# teensyShield1_2.net
KiCad netlist of a schematic drawn in EAGLE
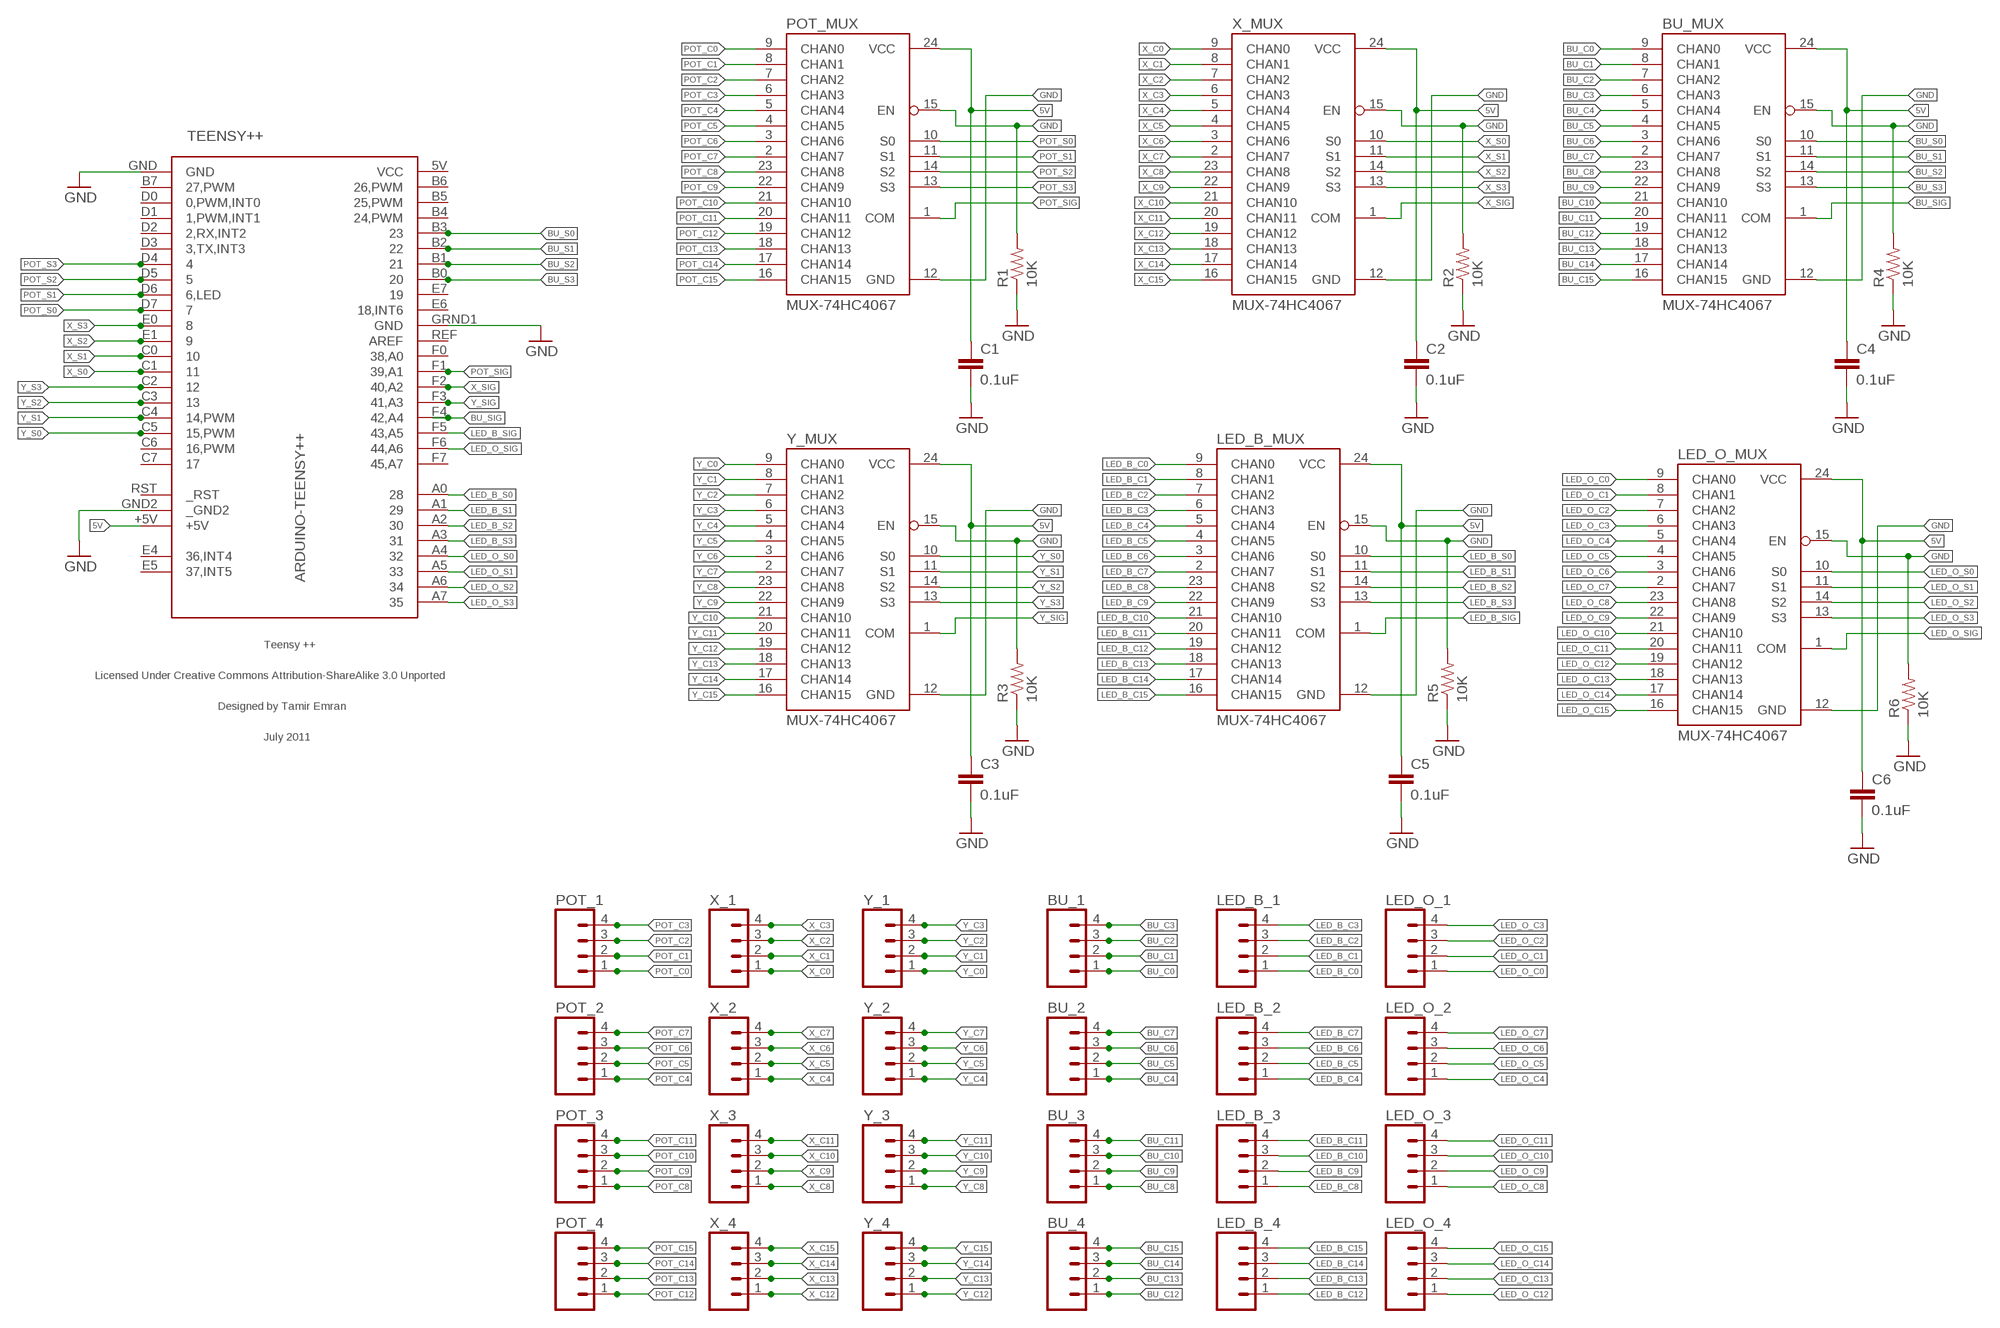
[diagram p0: schematic, sheet 1]

(export (version "E")
  (design (tool "Eeschema 10.0.6"))
  (components
    (comp (ref "BU_1")
      (value "M04NO_SILK_ALL_ROUND")
      (footprint "eagle-import:1X04_NO_SILK_ALL_ROUND")
      (libsource (lib "eagle-import") (part "M04NO_SILK_ALL_ROUND"))
    )
    (comp (ref "BU_2")
      (value "M04NO_SILK_ALL_ROUND")
      (footprint "eagle-import:1X04_NO_SILK_ALL_ROUND")
      (libsource (lib "eagle-import") (part "M04NO_SILK_ALL_ROUND"))
    )
    (comp (ref "BU_3")
      (value "M04NO_SILK_ALL_ROUND")
      (footprint "eagle-import:1X04_NO_SILK_ALL_ROUND")
      (libsource (lib "eagle-import") (part "M04NO_SILK_ALL_ROUND"))
    )
    (comp (ref "BU_4")
      (value "M04NO_SILK_ALL_ROUND")
      (footprint "eagle-import:1X04_NO_SILK_ALL_ROUND")
      (libsource (lib "eagle-import") (part "M04NO_SILK_ALL_ROUND"))
    )
    (comp (ref "BU_MUX")
      (value "MUX-74HC4067")
      (footprint "eagle-import:SSOP24")
      (libsource (lib "eagle-import") (part "MUX-74HC4067SMD"))
    )
    (comp (ref "C1")
      (value "0.1uF")
      (footprint "eagle-import:0603")
      (libsource (lib "eagle-import") (part "CAP0603"))
    )
    (comp (ref "C2")
      (value "0.1uF")
      (footprint "eagle-import:0603")
      (libsource (lib "eagle-import") (part "CAP0603"))
    )
    (comp (ref "C3")
      (value "0.1uF")
      (footprint "eagle-import:0603")
      (libsource (lib "eagle-import") (part "CAP0603"))
    )
    (comp (ref "C4")
      (value "0.1uF")
      (footprint "eagle-import:0603")
      (libsource (lib "eagle-import") (part "CAP0603"))
    )
    (comp (ref "C5")
      (value "0.1uF")
      (footprint "eagle-import:0603")
      (libsource (lib "eagle-import") (part "CAP0603"))
    )
    (comp (ref "C6")
      (value "0.1uF")
      (footprint "eagle-import:0603")
      (libsource (lib "eagle-import") (part "CAP0603"))
    )
    (comp (ref "LED_B_1")
      (value "M04NO_SILK_ALL_ROUND")
      (footprint "eagle-import:1X04_NO_SILK_ALL_ROUND")
      (libsource (lib "eagle-import") (part "M04NO_SILK_ALL_ROUND"))
    )
    (comp (ref "LED_B_2")
      (value "M04NO_SILK_ALL_ROUND")
      (footprint "eagle-import:1X04_NO_SILK_ALL_ROUND")
      (libsource (lib "eagle-import") (part "M04NO_SILK_ALL_ROUND"))
    )
    (comp (ref "LED_B_3")
      (value "M04NO_SILK_ALL_ROUND")
      (footprint "eagle-import:1X04_NO_SILK_ALL_ROUND")
      (libsource (lib "eagle-import") (part "M04NO_SILK_ALL_ROUND"))
    )
    (comp (ref "LED_B_4")
      (value "M04NO_SILK_ALL_ROUND")
      (footprint "eagle-import:1X04_NO_SILK_ALL_ROUND")
      (libsource (lib "eagle-import") (part "M04NO_SILK_ALL_ROUND"))
    )
    (comp (ref "LED_B_MUX")
      (value "MUX-74HC4067")
      (footprint "eagle-import:SSOP24")
      (libsource (lib "eagle-import") (part "MUX-74HC4067SMD"))
    )
    (comp (ref "LED_O_1")
      (value "M04NO_SILK_ALL_ROUND")
      (footprint "eagle-import:1X04_NO_SILK_ALL_ROUND")
      (libsource (lib "eagle-import") (part "M04NO_SILK_ALL_ROUND"))
    )
    (comp (ref "LED_O_2")
      (value "M04NO_SILK_ALL_ROUND")
      (footprint "eagle-import:1X04_NO_SILK_ALL_ROUND")
      (libsource (lib "eagle-import") (part "M04NO_SILK_ALL_ROUND"))
    )
    (comp (ref "LED_O_3")
      (value "M04NO_SILK_ALL_ROUND")
      (footprint "eagle-import:1X04_NO_SILK_ALL_ROUND")
      (libsource (lib "eagle-import") (part "M04NO_SILK_ALL_ROUND"))
    )
    (comp (ref "LED_O_4")
      (value "M04NO_SILK_ALL_ROUND")
      (footprint "eagle-import:1X04_NO_SILK_ALL_ROUND")
      (libsource (lib "eagle-import") (part "M04NO_SILK_ALL_ROUND"))
    )
    (comp (ref "LED_O_MUX")
      (value "MUX-74HC4067")
      (footprint "eagle-import:SSOP24")
      (libsource (lib "eagle-import") (part "MUX-74HC4067SMD"))
    )
    (comp (ref "POT_1")
      (value "M04NO_SILK_ALL_ROUND")
      (footprint "eagle-import:1X04_NO_SILK_ALL_ROUND")
      (libsource (lib "eagle-import") (part "M04NO_SILK_ALL_ROUND"))
    )
    (comp (ref "POT_2")
      (value "M04NO_SILK_ALL_ROUND")
      (footprint "eagle-import:1X04_NO_SILK_ALL_ROUND")
      (libsource (lib "eagle-import") (part "M04NO_SILK_ALL_ROUND"))
    )
    (comp (ref "POT_3")
      (value "M04NO_SILK_ALL_ROUND")
      (footprint "eagle-import:1X04_NO_SILK_ALL_ROUND")
      (libsource (lib "eagle-import") (part "M04NO_SILK_ALL_ROUND"))
    )
    (comp (ref "POT_4")
      (value "M04NO_SILK_ALL_ROUND")
      (footprint "eagle-import:1X04_NO_SILK_ALL_ROUND")
      (libsource (lib "eagle-import") (part "M04NO_SILK_ALL_ROUND"))
    )
    (comp (ref "POT_MUX")
      (value "MUX-74HC4067")
      (footprint "eagle-import:SSOP24")
      (libsource (lib "eagle-import") (part "MUX-74HC4067SMD"))
    )
    (comp (ref "R1")
      (value "10K")
      (footprint "eagle-import:0603")
      (libsource (lib "eagle-import") (part "RESISTOR0603"))
    )
    (comp (ref "R2")
      (value "10K")
      (footprint "eagle-import:0603")
      (libsource (lib "eagle-import") (part "RESISTOR0603"))
    )
    (comp (ref "R3")
      (value "10K")
      (footprint "eagle-import:0603")
      (libsource (lib "eagle-import") (part "RESISTOR0603"))
    )
    (comp (ref "R4")
      (value "10K")
      (footprint "eagle-import:0603")
      (libsource (lib "eagle-import") (part "RESISTOR0603"))
    )
    (comp (ref "R5")
      (value "10K")
      (footprint "eagle-import:0603")
      (libsource (lib "eagle-import") (part "RESISTOR0603"))
    )
    (comp (ref "R6")
      (value "10K")
      (footprint "eagle-import:0603")
      (libsource (lib "eagle-import") (part "RESISTOR0603"))
    )
    (comp (ref "TEENSY++")
      (value "ARDUINO-TEENSY++")
      (footprint "eagle-import:TEENSY++")
      (libsource (lib "eagle-import") (part "ARDUINO-TEENSY++"))
    )
    (comp (ref "X_1")
      (value "M04NO_SILK_ALL_ROUND")
      (footprint "eagle-import:1X04_NO_SILK_ALL_ROUND")
      (libsource (lib "eagle-import") (part "M04NO_SILK_ALL_ROUND"))
    )
    (comp (ref "X_2")
      (value "M04NO_SILK_ALL_ROUND")
      (footprint "eagle-import:1X04_NO_SILK_ALL_ROUND")
      (libsource (lib "eagle-import") (part "M04NO_SILK_ALL_ROUND"))
    )
    (comp (ref "X_3")
      (value "M04NO_SILK_ALL_ROUND")
      (footprint "eagle-import:1X04_NO_SILK_ALL_ROUND")
      (libsource (lib "eagle-import") (part "M04NO_SILK_ALL_ROUND"))
    )
    (comp (ref "X_4")
      (value "M04NO_SILK_ALL_ROUND")
      (footprint "eagle-import:1X04_NO_SILK_ALL_ROUND")
      (libsource (lib "eagle-import") (part "M04NO_SILK_ALL_ROUND"))
    )
    (comp (ref "X_MUX")
      (value "MUX-74HC4067")
      (footprint "eagle-import:SSOP24")
      (libsource (lib "eagle-import") (part "MUX-74HC4067SMD"))
    )
    (comp (ref "Y_1")
      (value "M04NO_SILK_ALL_ROUND")
      (footprint "eagle-import:1X04_NO_SILK_ALL_ROUND")
      (libsource (lib "eagle-import") (part "M04NO_SILK_ALL_ROUND"))
    )
    (comp (ref "Y_2")
      (value "M04NO_SILK_ALL_ROUND")
      (footprint "eagle-import:1X04_NO_SILK_ALL_ROUND")
      (libsource (lib "eagle-import") (part "M04NO_SILK_ALL_ROUND"))
    )
    (comp (ref "Y_3")
      (value "M04NO_SILK_ALL_ROUND")
      (footprint "eagle-import:1X04_NO_SILK_ALL_ROUND")
      (libsource (lib "eagle-import") (part "M04NO_SILK_ALL_ROUND"))
    )
    (comp (ref "Y_4")
      (value "M04NO_SILK_ALL_ROUND")
      (footprint "eagle-import:1X04_NO_SILK_ALL_ROUND")
      (libsource (lib "eagle-import") (part "M04NO_SILK_ALL_ROUND"))
    )
    (comp (ref "Y_MUX")
      (value "MUX-74HC4067")
      (footprint "eagle-import:SSOP24")
      (libsource (lib "eagle-import") (part "MUX-74HC4067SMD"))
    )
  )
  (nets
    (net (code "1") (name "/VCC") (class "Default")
      (node (ref "TEENSY++") (pin "5V") (pinfunction "VCC_5V") (pintype "power_in"))
    )
    (net (code "2") (name "5V") (class "Default")
      (node (ref "BU_MUX") (pin "24") (pinfunction "VCC_24") (pintype "bidirectional"))
      (node (ref "C1") (pin "1") (pinfunction "1_1") (pintype "passive"))
      (node (ref "C2") (pin "1") (pinfunction "1_1") (pintype "passive"))
      (node (ref "C3") (pin "1") (pinfunction "1_1") (pintype "passive"))
      (node (ref "C4") (pin "1") (pinfunction "1_1") (pintype "passive"))
      (node (ref "C5") (pin "1") (pinfunction "1_1") (pintype "passive"))
      (node (ref "C6") (pin "1") (pinfunction "1_1") (pintype "passive"))
      (node (ref "LED_B_MUX") (pin "24") (pinfunction "VCC_24") (pintype "bidirectional"))
      (node (ref "LED_O_MUX") (pin "24") (pinfunction "VCC_24") (pintype "bidirectional"))
      (node (ref "POT_MUX") (pin "24") (pinfunction "VCC_24") (pintype "bidirectional"))
      (node (ref "X_MUX") (pin "24") (pinfunction "VCC_24") (pintype "bidirectional"))
      (node (ref "Y_MUX") (pin "24") (pinfunction "VCC_24") (pintype "bidirectional"))
    )
    (net (code "3") (name "BU_C0") (class "Default")
      (node (ref "BU_1") (pin "1") (pinfunction "1_1") (pintype "passive"))
      (node (ref "BU_MUX") (pin "9") (pinfunction "CHAN0_9") (pintype "bidirectional"))
    )
    (net (code "4") (name "BU_C1") (class "Default")
      (node (ref "BU_1") (pin "2") (pinfunction "2_2") (pintype "passive"))
      (node (ref "BU_MUX") (pin "8") (pinfunction "CHAN1_8") (pintype "bidirectional"))
    )
    (net (code "5") (name "BU_C2") (class "Default")
      (node (ref "BU_1") (pin "3") (pinfunction "3_3") (pintype "passive"))
      (node (ref "BU_MUX") (pin "7") (pinfunction "CHAN2_7") (pintype "bidirectional"))
    )
    (net (code "6") (name "BU_C3") (class "Default")
      (node (ref "BU_1") (pin "4") (pinfunction "4_4") (pintype "passive"))
      (node (ref "BU_MUX") (pin "6") (pinfunction "CHAN3_6") (pintype "bidirectional"))
    )
    (net (code "7") (name "BU_C4") (class "Default")
      (node (ref "BU_2") (pin "1") (pinfunction "1_1") (pintype "passive"))
      (node (ref "BU_MUX") (pin "5") (pinfunction "CHAN4_5") (pintype "bidirectional"))
    )
    (net (code "8") (name "BU_C5") (class "Default")
      (node (ref "BU_2") (pin "2") (pinfunction "2_2") (pintype "passive"))
      (node (ref "BU_MUX") (pin "4") (pinfunction "CHAN5_4") (pintype "bidirectional"))
    )
    (net (code "9") (name "BU_C6") (class "Default")
      (node (ref "BU_2") (pin "3") (pinfunction "3_3") (pintype "passive"))
      (node (ref "BU_MUX") (pin "3") (pinfunction "CHAN6_3") (pintype "bidirectional"))
    )
    (net (code "10") (name "BU_C7") (class "Default")
      (node (ref "BU_2") (pin "4") (pinfunction "4_4") (pintype "passive"))
      (node (ref "BU_MUX") (pin "2") (pinfunction "CHAN7_2") (pintype "bidirectional"))
    )
    (net (code "11") (name "BU_C8") (class "Default")
      (node (ref "BU_3") (pin "1") (pinfunction "1_1") (pintype "passive"))
      (node (ref "BU_MUX") (pin "23") (pinfunction "CHAN8_23") (pintype "bidirectional"))
    )
    (net (code "12") (name "BU_C9") (class "Default")
      (node (ref "BU_3") (pin "2") (pinfunction "2_2") (pintype "passive"))
      (node (ref "BU_MUX") (pin "22") (pinfunction "CHAN9_22") (pintype "bidirectional"))
    )
    (net (code "13") (name "BU_C10") (class "Default")
      (node (ref "BU_3") (pin "3") (pinfunction "3_3") (pintype "passive"))
      (node (ref "BU_MUX") (pin "21") (pinfunction "CHAN10_21") (pintype "bidirectional"))
    )
    (net (code "14") (name "BU_C11") (class "Default")
      (node (ref "BU_3") (pin "4") (pinfunction "4_4") (pintype "passive"))
      (node (ref "BU_MUX") (pin "20") (pinfunction "CHAN11_20") (pintype "bidirectional"))
    )
    (net (code "15") (name "BU_C12") (class "Default")
      (node (ref "BU_4") (pin "1") (pinfunction "1_1") (pintype "passive"))
      (node (ref "BU_MUX") (pin "19") (pinfunction "CHAN12_19") (pintype "bidirectional"))
    )
    (net (code "16") (name "BU_C13") (class "Default")
      (node (ref "BU_4") (pin "2") (pinfunction "2_2") (pintype "passive"))
      (node (ref "BU_MUX") (pin "18") (pinfunction "CHAN13_18") (pintype "bidirectional"))
    )
    (net (code "17") (name "BU_C14") (class "Default")
      (node (ref "BU_4") (pin "3") (pinfunction "3_3") (pintype "passive"))
      (node (ref "BU_MUX") (pin "17") (pinfunction "CHAN14_17") (pintype "bidirectional"))
    )
    (net (code "18") (name "BU_C15") (class "Default")
      (node (ref "BU_4") (pin "4") (pinfunction "4_4") (pintype "passive"))
      (node (ref "BU_MUX") (pin "16") (pinfunction "CHAN15_16") (pintype "bidirectional"))
    )
    (net (code "19") (name "BU_S0") (class "Default")
      (node (ref "BU_MUX") (pin "10") (pinfunction "S0_10") (pintype "input"))
      (node (ref "TEENSY++") (pin "B3") (pinfunction "23_B3") (pintype "bidirectional"))
    )
    (net (code "20") (name "BU_S1") (class "Default")
      (node (ref "BU_MUX") (pin "11") (pinfunction "S1_11") (pintype "input"))
      (node (ref "TEENSY++") (pin "B2") (pinfunction "22_B2") (pintype "bidirectional"))
    )
    (net (code "21") (name "BU_S2") (class "Default")
      (node (ref "BU_MUX") (pin "14") (pinfunction "S2_14") (pintype "input"))
      (node (ref "TEENSY++") (pin "B1") (pinfunction "21_B1") (pintype "bidirectional"))
    )
    (net (code "22") (name "BU_S3") (class "Default")
      (node (ref "BU_MUX") (pin "13") (pinfunction "S3_13") (pintype "input"))
      (node (ref "TEENSY++") (pin "B0") (pinfunction "20_B0") (pintype "bidirectional"))
    )
    (net (code "23") (name "BU_SIG") (class "Default")
      (node (ref "BU_MUX") (pin "1") (pinfunction "COM_1") (pintype "bidirectional"))
      (node (ref "TEENSY++") (pin "F4") (pinfunction "42,A4_F4") (pintype "bidirectional"))
    )
    (net (code "24") (name "GND") (class "Default")
      (node (ref "BU_MUX") (pin "12") (pinfunction "GND_12") (pintype "bidirectional"))
      (node (ref "BU_MUX") (pin "15") (pinfunction "EN_15") (pintype "input"))
      (node (ref "C1") (pin "2") (pinfunction "2_2") (pintype "passive"))
      (node (ref "C2") (pin "2") (pinfunction "2_2") (pintype "passive"))
      (node (ref "C3") (pin "2") (pinfunction "2_2") (pintype "passive"))
      (node (ref "C4") (pin "2") (pinfunction "2_2") (pintype "passive"))
      (node (ref "C5") (pin "2") (pinfunction "2_2") (pintype "passive"))
      (node (ref "C6") (pin "2") (pinfunction "2_2") (pintype "passive"))
      (node (ref "LED_B_MUX") (pin "12") (pinfunction "GND_12") (pintype "bidirectional"))
      (node (ref "LED_B_MUX") (pin "15") (pinfunction "EN_15") (pintype "input"))
      (node (ref "LED_O_MUX") (pin "12") (pinfunction "GND_12") (pintype "bidirectional"))
      (node (ref "LED_O_MUX") (pin "15") (pinfunction "EN_15") (pintype "input"))
      (node (ref "POT_MUX") (pin "12") (pinfunction "GND_12") (pintype "bidirectional"))
      (node (ref "POT_MUX") (pin "15") (pinfunction "EN_15") (pintype "input"))
      (node (ref "R1") (pin "1") (pinfunction "1_1") (pintype "passive"))
      (node (ref "R1") (pin "2") (pinfunction "2_2") (pintype "passive"))
      (node (ref "R2") (pin "1") (pinfunction "1_1") (pintype "passive"))
      (node (ref "R2") (pin "2") (pinfunction "2_2") (pintype "passive"))
      (node (ref "R3") (pin "1") (pinfunction "1_1") (pintype "passive"))
      (node (ref "R3") (pin "2") (pinfunction "2_2") (pintype "passive"))
      (node (ref "R4") (pin "1") (pinfunction "1_1") (pintype "passive"))
      (node (ref "R4") (pin "2") (pinfunction "2_2") (pintype "passive"))
      (node (ref "R5") (pin "1") (pinfunction "1_1") (pintype "passive"))
      (node (ref "R5") (pin "2") (pinfunction "2_2") (pintype "passive"))
      (node (ref "R6") (pin "1") (pinfunction "1_1") (pintype "passive"))
      (node (ref "R6") (pin "2") (pinfunction "2_2") (pintype "passive"))
      (node (ref "TEENSY++") (pin "GND") (pinfunction "GND_GND") (pintype "power_in"))
      (node (ref "TEENSY++") (pin "GND2") (pinfunction "_GND2_GND2") (pintype "power_in"))
      (node (ref "TEENSY++") (pin "GRND1") (pinfunction "GND_GRND1") (pintype "power_in"))
      (node (ref "X_MUX") (pin "12") (pinfunction "GND_12") (pintype "bidirectional"))
      (node (ref "X_MUX") (pin "15") (pinfunction "EN_15") (pintype "input"))
      (node (ref "Y_MUX") (pin "12") (pinfunction "GND_12") (pintype "bidirectional"))
      (node (ref "Y_MUX") (pin "15") (pinfunction "EN_15") (pintype "input"))
    )
    (net (code "25") (name "LED_B_C0") (class "Default")
      (node (ref "LED_B_1") (pin "1") (pinfunction "1_1") (pintype "passive"))
      (node (ref "LED_B_MUX") (pin "9") (pinfunction "CHAN0_9") (pintype "bidirectional"))
    )
    (net (code "26") (name "LED_B_C1") (class "Default")
      (node (ref "LED_B_1") (pin "2") (pinfunction "2_2") (pintype "passive"))
      (node (ref "LED_B_MUX") (pin "8") (pinfunction "CHAN1_8") (pintype "bidirectional"))
    )
    (net (code "27") (name "LED_B_C2") (class "Default")
      (node (ref "LED_B_1") (pin "3") (pinfunction "3_3") (pintype "passive"))
      (node (ref "LED_B_MUX") (pin "7") (pinfunction "CHAN2_7") (pintype "bidirectional"))
    )
    (net (code "28") (name "LED_B_C3") (class "Default")
      (node (ref "LED_B_1") (pin "4") (pinfunction "4_4") (pintype "passive"))
      (node (ref "LED_B_MUX") (pin "6") (pinfunction "CHAN3_6") (pintype "bidirectional"))
    )
    (net (code "29") (name "LED_B_C4") (class "Default")
      (node (ref "LED_B_2") (pin "1") (pinfunction "1_1") (pintype "passive"))
      (node (ref "LED_B_MUX") (pin "5") (pinfunction "CHAN4_5") (pintype "bidirectional"))
    )
    (net (code "30") (name "LED_B_C5") (class "Default")
      (node (ref "LED_B_2") (pin "2") (pinfunction "2_2") (pintype "passive"))
      (node (ref "LED_B_MUX") (pin "4") (pinfunction "CHAN5_4") (pintype "bidirectional"))
    )
    (net (code "31") (name "LED_B_C6") (class "Default")
      (node (ref "LED_B_2") (pin "3") (pinfunction "3_3") (pintype "passive"))
      (node (ref "LED_B_MUX") (pin "3") (pinfunction "CHAN6_3") (pintype "bidirectional"))
    )
    (net (code "32") (name "LED_B_C7") (class "Default")
      (node (ref "LED_B_2") (pin "4") (pinfunction "4_4") (pintype "passive"))
      (node (ref "LED_B_MUX") (pin "2") (pinfunction "CHAN7_2") (pintype "bidirectional"))
    )
    (net (code "33") (name "LED_B_C8") (class "Default")
      (node (ref "LED_B_3") (pin "1") (pinfunction "1_1") (pintype "passive"))
      (node (ref "LED_B_MUX") (pin "23") (pinfunction "CHAN8_23") (pintype "bidirectional"))
    )
    (net (code "34") (name "LED_B_C9") (class "Default")
      (node (ref "LED_B_3") (pin "2") (pinfunction "2_2") (pintype "passive"))
      (node (ref "LED_B_MUX") (pin "22") (pinfunction "CHAN9_22") (pintype "bidirectional"))
    )
    (net (code "35") (name "LED_B_C10") (class "Default")
      (node (ref "LED_B_3") (pin "3") (pinfunction "3_3") (pintype "passive"))
      (node (ref "LED_B_MUX") (pin "21") (pinfunction "CHAN10_21") (pintype "bidirectional"))
    )
    (net (code "36") (name "LED_B_C11") (class "Default")
      (node (ref "LED_B_3") (pin "4") (pinfunction "4_4") (pintype "passive"))
      (node (ref "LED_B_MUX") (pin "20") (pinfunction "CHAN11_20") (pintype "bidirectional"))
    )
    (net (code "37") (name "LED_B_C12") (class "Default")
      (node (ref "LED_B_4") (pin "1") (pinfunction "1_1") (pintype "passive"))
      (node (ref "LED_B_MUX") (pin "19") (pinfunction "CHAN12_19") (pintype "bidirectional"))
    )
    (net (code "38") (name "LED_B_C13") (class "Default")
      (node (ref "LED_B_4") (pin "2") (pinfunction "2_2") (pintype "passive"))
      (node (ref "LED_B_MUX") (pin "18") (pinfunction "CHAN13_18") (pintype "bidirectional"))
    )
    (net (code "39") (name "LED_B_C14") (class "Default")
      (node (ref "LED_B_4") (pin "3") (pinfunction "3_3") (pintype "passive"))
      (node (ref "LED_B_MUX") (pin "17") (pinfunction "CHAN14_17") (pintype "bidirectional"))
    )
    (net (code "40") (name "LED_B_C15") (class "Default")
      (node (ref "LED_B_4") (pin "4") (pinfunction "4_4") (pintype "passive"))
      (node (ref "LED_B_MUX") (pin "16") (pinfunction "CHAN15_16") (pintype "bidirectional"))
    )
    (net (code "41") (name "LED_B_S0") (class "Default")
      (node (ref "LED_B_MUX") (pin "10") (pinfunction "S0_10") (pintype "input"))
      (node (ref "TEENSY++") (pin "A0") (pinfunction "28_A0") (pintype "bidirectional"))
    )
    (net (code "42") (name "LED_B_S1") (class "Default")
      (node (ref "LED_B_MUX") (pin "11") (pinfunction "S1_11") (pintype "input"))
      (node (ref "TEENSY++") (pin "A1") (pinfunction "29_A1") (pintype "bidirectional"))
    )
    (net (code "43") (name "LED_B_S2") (class "Default")
      (node (ref "LED_B_MUX") (pin "14") (pinfunction "S2_14") (pintype "input"))
      (node (ref "TEENSY++") (pin "A2") (pinfunction "30_A2") (pintype "bidirectional"))
    )
    (net (code "44") (name "LED_B_S3") (class "Default")
      (node (ref "LED_B_MUX") (pin "13") (pinfunction "S3_13") (pintype "input"))
      (node (ref "TEENSY++") (pin "A3") (pinfunction "31_A3") (pintype "bidirectional"))
    )
    (net (code "45") (name "LED_B_SIG") (class "Default")
      (node (ref "LED_B_MUX") (pin "1") (pinfunction "COM_1") (pintype "bidirectional"))
    )
    (net (code "46") (name "LED_O_C0") (class "Default")
      (node (ref "LED_O_1") (pin "1") (pinfunction "1_1") (pintype "passive"))
      (node (ref "LED_O_MUX") (pin "9") (pinfunction "CHAN0_9") (pintype "bidirectional"))
    )
    (net (code "47") (name "LED_O_C1") (class "Default")
      (node (ref "LED_O_1") (pin "2") (pinfunction "2_2") (pintype "passive"))
      (node (ref "LED_O_MUX") (pin "8") (pinfunction "CHAN1_8") (pintype "bidirectional"))
    )
    (net (code "48") (name "LED_O_C2") (class "Default")
      (node (ref "LED_O_1") (pin "3") (pinfunction "3_3") (pintype "passive"))
      (node (ref "LED_O_MUX") (pin "7") (pinfunction "CHAN2_7") (pintype "bidirectional"))
    )
    (net (code "49") (name "LED_O_C3") (class "Default")
      (node (ref "LED_O_1") (pin "4") (pinfunction "4_4") (pintype "passive"))
      (node (ref "LED_O_MUX") (pin "6") (pinfunction "CHAN3_6") (pintype "bidirectional"))
    )
    (net (code "50") (name "LED_O_C4") (class "Default")
      (node (ref "LED_O_2") (pin "1") (pinfunction "1_1") (pintype "passive"))
      (node (ref "LED_O_MUX") (pin "5") (pinfunction "CHAN4_5") (pintype "bidirectional"))
    )
    (net (code "51") (name "LED_O_C5") (class "Default")
      (node (ref "LED_O_2") (pin "2") (pinfunction "2_2") (pintype "passive"))
      (node (ref "LED_O_MUX") (pin "4") (pinfunction "CHAN5_4") (pintype "bidirectional"))
    )
    (net (code "52") (name "LED_O_C6") (class "Default")
      (node (ref "LED_O_2") (pin "3") (pinfunction "3_3") (pintype "passive"))
      (node (ref "LED_O_MUX") (pin "3") (pinfunction "CHAN6_3") (pintype "bidirectional"))
    )
    (net (code "53") (name "LED_O_C7") (class "Default")
      (node (ref "LED_O_2") (pin "4") (pinfunction "4_4") (pintype "passive"))
      (node (ref "LED_O_MUX") (pin "2") (pinfunction "CHAN7_2") (pintype "bidirectional"))
    )
    (net (code "54") (name "LED_O_C8") (class "Default")
      (node (ref "LED_O_3") (pin "1") (pinfunction "1_1") (pintype "passive"))
      (node (ref "LED_O_MUX") (pin "23") (pinfunction "CHAN8_23") (pintype "bidirectional"))
    )
    (net (code "55") (name "LED_O_C9") (class "Default")
      (node (ref "LED_O_3") (pin "2") (pinfunction "2_2") (pintype "passive"))
      (node (ref "LED_O_MUX") (pin "22") (pinfunction "CHAN9_22") (pintype "bidirectional"))
    )
    (net (code "56") (name "LED_O_C10") (class "Default")
      (node (ref "LED_O_3") (pin "3") (pinfunction "3_3") (pintype "passive"))
      (node (ref "LED_O_MUX") (pin "21") (pinfunction "CHAN10_21") (pintype "bidirectional"))
    )
    (net (code "57") (name "LED_O_C11") (class "Default")
      (node (ref "LED_O_3") (pin "4") (pinfunction "4_4") (pintype "passive"))
      (node (ref "LED_O_MUX") (pin "20") (pinfunction "CHAN11_20") (pintype "bidirectional"))
    )
    (net (code "58") (name "LED_O_C12") (class "Default")
      (node (ref "LED_O_4") (pin "1") (pinfunction "1_1") (pintype "passive"))
      (node (ref "LED_O_MUX") (pin "19") (pinfunction "CHAN12_19") (pintype "bidirectional"))
    )
    (net (code "59") (name "LED_O_C13") (class "Default")
      (node (ref "LED_O_4") (pin "2") (pinfunction "2_2") (pintype "passive"))
      (node (ref "LED_O_MUX") (pin "18") (pinfunction "CHAN13_18") (pintype "bidirectional"))
    )
    (net (code "60") (name "LED_O_C14") (class "Default")
      (node (ref "LED_O_4") (pin "3") (pinfunction "3_3") (pintype "passive"))
      (node (ref "LED_O_MUX") (pin "17") (pinfunction "CHAN14_17") (pintype "bidirectional"))
    )
    (net (code "61") (name "LED_O_C15") (class "Default")
      (node (ref "LED_O_4") (pin "4") (pinfunction "4_4") (pintype "passive"))
      (node (ref "LED_O_MUX") (pin "16") (pinfunction "CHAN15_16") (pintype "bidirectional"))
    )
    (net (code "62") (name "LED_O_S0") (class "Default")
      (node (ref "LED_O_MUX") (pin "10") (pinfunction "S0_10") (pintype "input"))
      (node (ref "TEENSY++") (pin "A4") (pinfunction "32_A4") (pintype "bidirectional"))
    )
    (net (code "63") (name "LED_O_S1") (class "Default")
      (node (ref "LED_O_MUX") (pin "11") (pinfunction "S1_11") (pintype "input"))
      (node (ref "TEENSY++") (pin "A5") (pinfunction "33_A5") (pintype "bidirectional"))
    )
    (net (code "64") (name "LED_O_S2") (class "Default")
      (node (ref "LED_O_MUX") (pin "14") (pinfunction "S2_14") (pintype "input"))
      (node (ref "TEENSY++") (pin "A6") (pinfunction "34_A6") (pintype "bidirectional"))
    )
    (net (code "65") (name "LED_O_S3") (class "Default")
      (node (ref "LED_O_MUX") (pin "13") (pinfunction "S3_13") (pintype "input"))
      (node (ref "TEENSY++") (pin "A7") (pinfunction "35_A7") (pintype "bidirectional"))
    )
    (net (code "66") (name "LED_O_SIG") (class "Default")
      (node (ref "LED_O_MUX") (pin "1") (pinfunction "COM_1") (pintype "bidirectional"))
    )
    (net (code "67") (name "POT_C0") (class "Default")
      (node (ref "POT_1") (pin "1") (pinfunction "1_1") (pintype "passive"))
      (node (ref "POT_MUX") (pin "9") (pinfunction "CHAN0_9") (pintype "bidirectional"))
    )
    (net (code "68") (name "POT_C1") (class "Default")
      (node (ref "POT_1") (pin "2") (pinfunction "2_2") (pintype "passive"))
      (node (ref "POT_MUX") (pin "8") (pinfunction "CHAN1_8") (pintype "bidirectional"))
    )
    (net (code "69") (name "POT_C2") (class "Default")
      (node (ref "POT_1") (pin "3") (pinfunction "3_3") (pintype "passive"))
      (node (ref "POT_MUX") (pin "7") (pinfunction "CHAN2_7") (pintype "bidirectional"))
    )
    (net (code "70") (name "POT_C3") (class "Default")
      (node (ref "POT_1") (pin "4") (pinfunction "4_4") (pintype "passive"))
      (node (ref "POT_MUX") (pin "6") (pinfunction "CHAN3_6") (pintype "bidirectional"))
    )
    (net (code "71") (name "POT_C4") (class "Default")
      (node (ref "POT_2") (pin "1") (pinfunction "1_1") (pintype "passive"))
      (node (ref "POT_MUX") (pin "5") (pinfunction "CHAN4_5") (pintype "bidirectional"))
    )
    (net (code "72") (name "POT_C5") (class "Default")
      (node (ref "POT_2") (pin "2") (pinfunction "2_2") (pintype "passive"))
      (node (ref "POT_MUX") (pin "4") (pinfunction "CHAN5_4") (pintype "bidirectional"))
    )
    (net (code "73") (name "POT_C6") (class "Default")
      (node (ref "POT_2") (pin "3") (pinfunction "3_3") (pintype "passive"))
      (node (ref "POT_MUX") (pin "3") (pinfunction "CHAN6_3") (pintype "bidirectional"))
    )
    (net (code "74") (name "POT_C7") (class "Default")
      (node (ref "POT_2") (pin "4") (pinfunction "4_4") (pintype "passive"))
      (node (ref "POT_MUX") (pin "2") (pinfunction "CHAN7_2") (pintype "bidirectional"))
    )
    (net (code "75") (name "POT_C8") (class "Default")
      (node (ref "POT_3") (pin "1") (pinfunction "1_1") (pintype "passive"))
      (node (ref "POT_MUX") (pin "23") (pinfunction "CHAN8_23") (pintype "bidirectional"))
    )
    (net (code "76") (name "POT_C9") (class "Default")
      (node (ref "POT_3") (pin "2") (pinfunction "2_2") (pintype "passive"))
      (node (ref "POT_MUX") (pin "22") (pinfunction "CHAN9_22") (pintype "bidirectional"))
    )
    (net (code "77") (name "POT_C10") (class "Default")
      (node (ref "POT_3") (pin "3") (pinfunction "3_3") (pintype "passive"))
      (node (ref "POT_MUX") (pin "21") (pinfunction "CHAN10_21") (pintype "bidirectional"))
    )
    (net (code "78") (name "POT_C11") (class "Default")
      (node (ref "POT_3") (pin "4") (pinfunction "4_4") (pintype "passive"))
      (node (ref "POT_MUX") (pin "20") (pinfunction "CHAN11_20") (pintype "bidirectional"))
    )
    (net (code "79") (name "POT_C12") (class "Default")
      (node (ref "POT_4") (pin "1") (pinfunction "1_1") (pintype "passive"))
      (node (ref "POT_MUX") (pin "19") (pinfunction "CHAN12_19") (pintype "bidirectional"))
    )
    (net (code "80") (name "POT_C13") (class "Default")
      (node (ref "POT_4") (pin "2") (pinfunction "2_2") (pintype "passive"))
      (node (ref "POT_MUX") (pin "18") (pinfunction "CHAN13_18") (pintype "bidirectional"))
    )
    (net (code "81") (name "POT_C14") (class "Default")
      (node (ref "POT_4") (pin "3") (pinfunction "3_3") (pintype "passive"))
      (node (ref "POT_MUX") (pin "17") (pinfunction "CHAN14_17") (pintype "bidirectional"))
    )
    (net (code "82") (name "POT_C15") (class "Default")
      (node (ref "POT_4") (pin "4") (pinfunction "4_4") (pintype "passive"))
      (node (ref "POT_MUX") (pin "16") (pinfunction "CHAN15_16") (pintype "bidirectional"))
    )
    (net (code "83") (name "POT_S0") (class "Default")
      (node (ref "POT_MUX") (pin "10") (pinfunction "S0_10") (pintype "input"))
      (node (ref "TEENSY++") (pin "D7") (pinfunction "7_D7") (pintype "bidirectional"))
    )
    (net (code "84") (name "POT_S1") (class "Default")
      (node (ref "POT_MUX") (pin "11") (pinfunction "S1_11") (pintype "input"))
      (node (ref "TEENSY++") (pin "D6") (pinfunction "6,LED_D6") (pintype "bidirectional"))
    )
    (net (code "85") (name "POT_S2") (class "Default")
      (node (ref "POT_MUX") (pin "14") (pinfunction "S2_14") (pintype "input"))
      (node (ref "TEENSY++") (pin "D5") (pinfunction "5_D5") (pintype "bidirectional"))
    )
    (net (code "86") (name "POT_S3") (class "Default")
      (node (ref "POT_MUX") (pin "13") (pinfunction "S3_13") (pintype "input"))
      (node (ref "TEENSY++") (pin "D4") (pinfunction "4_D4") (pintype "bidirectional"))
    )
    (net (code "87") (name "POT_SIG") (class "Default")
      (node (ref "POT_MUX") (pin "1") (pinfunction "COM_1") (pintype "bidirectional"))
    )
    (net (code "88") (name "X_C0") (class "Default")
      (node (ref "X_1") (pin "1") (pinfunction "1_1") (pintype "passive"))
      (node (ref "X_MUX") (pin "9") (pinfunction "CHAN0_9") (pintype "bidirectional"))
    )
    (net (code "89") (name "X_C1") (class "Default")
      (node (ref "X_1") (pin "2") (pinfunction "2_2") (pintype "passive"))
      (node (ref "X_MUX") (pin "8") (pinfunction "CHAN1_8") (pintype "bidirectional"))
    )
    (net (code "90") (name "X_C2") (class "Default")
      (node (ref "X_1") (pin "3") (pinfunction "3_3") (pintype "passive"))
      (node (ref "X_MUX") (pin "7") (pinfunction "CHAN2_7") (pintype "bidirectional"))
    )
    (net (code "91") (name "X_C3") (class "Default")
      (node (ref "X_1") (pin "4") (pinfunction "4_4") (pintype "passive"))
      (node (ref "X_MUX") (pin "6") (pinfunction "CHAN3_6") (pintype "bidirectional"))
    )
    (net (code "92") (name "X_C4") (class "Default")
      (node (ref "X_2") (pin "1") (pinfunction "1_1") (pintype "passive"))
      (node (ref "X_MUX") (pin "5") (pinfunction "CHAN4_5") (pintype "bidirectional"))
    )
    (net (code "93") (name "X_C5") (class "Default")
      (node (ref "X_2") (pin "2") (pinfunction "2_2") (pintype "passive"))
      (node (ref "X_MUX") (pin "4") (pinfunction "CHAN5_4") (pintype "bidirectional"))
    )
    (net (code "94") (name "X_C6") (class "Default")
      (node (ref "X_2") (pin "3") (pinfunction "3_3") (pintype "passive"))
      (node (ref "X_MUX") (pin "3") (pinfunction "CHAN6_3") (pintype "bidirectional"))
    )
    (net (code "95") (name "X_C7") (class "Default")
      (node (ref "X_2") (pin "4") (pinfunction "4_4") (pintype "passive"))
      (node (ref "X_MUX") (pin "2") (pinfunction "CHAN7_2") (pintype "bidirectional"))
    )
    (net (code "96") (name "X_C8") (class "Default")
      (node (ref "X_3") (pin "1") (pinfunction "1_1") (pintype "passive"))
      (node (ref "X_MUX") (pin "23") (pinfunction "CHAN8_23") (pintype "bidirectional"))
    )
    (net (code "97") (name "X_C9") (class "Default")
      (node (ref "X_3") (pin "2") (pinfunction "2_2") (pintype "passive"))
      (node (ref "X_MUX") (pin "22") (pinfunction "CHAN9_22") (pintype "bidirectional"))
    )
    (net (code "98") (name "X_C10") (class "Default")
      (node (ref "X_3") (pin "3") (pinfunction "3_3") (pintype "passive"))
      (node (ref "X_MUX") (pin "21") (pinfunction "CHAN10_21") (pintype "bidirectional"))
    )
    (net (code "99") (name "X_C11") (class "Default")
      (node (ref "X_3") (pin "4") (pinfunction "4_4") (pintype "passive"))
      (node (ref "X_MUX") (pin "20") (pinfunction "CHAN11_20") (pintype "bidirectional"))
    )
    (net (code "100") (name "X_C12") (class "Default")
      (node (ref "X_4") (pin "1") (pinfunction "1_1") (pintype "passive"))
      (node (ref "X_MUX") (pin "19") (pinfunction "CHAN12_19") (pintype "bidirectional"))
    )
    (net (code "101") (name "X_C13") (class "Default")
      (node (ref "X_4") (pin "2") (pinfunction "2_2") (pintype "passive"))
      (node (ref "X_MUX") (pin "18") (pinfunction "CHAN13_18") (pintype "bidirectional"))
    )
    (net (code "102") (name "X_C14") (class "Default")
      (node (ref "X_4") (pin "3") (pinfunction "3_3") (pintype "passive"))
      (node (ref "X_MUX") (pin "17") (pinfunction "CHAN14_17") (pintype "bidirectional"))
    )
    (net (code "103") (name "X_C15") (class "Default")
      (node (ref "X_4") (pin "4") (pinfunction "4_4") (pintype "passive"))
      (node (ref "X_MUX") (pin "16") (pinfunction "CHAN15_16") (pintype "bidirectional"))
    )
    (net (code "104") (name "X_S0") (class "Default")
      (node (ref "TEENSY++") (pin "C1") (pinfunction "11_C1") (pintype "bidirectional"))
      (node (ref "X_MUX") (pin "10") (pinfunction "S0_10") (pintype "input"))
    )
    (net (code "105") (name "X_S1") (class "Default")
      (node (ref "TEENSY++") (pin "C0") (pinfunction "10_C0") (pintype "bidirectional"))
      (node (ref "X_MUX") (pin "11") (pinfunction "S1_11") (pintype "input"))
    )
    (net (code "106") (name "X_S2") (class "Default")
      (node (ref "TEENSY++") (pin "E1") (pinfunction "9_E1") (pintype "bidirectional"))
      (node (ref "X_MUX") (pin "14") (pinfunction "S2_14") (pintype "input"))
    )
    (net (code "107") (name "X_S3") (class "Default")
      (node (ref "TEENSY++") (pin "E0") (pinfunction "8_E0") (pintype "bidirectional"))
      (node (ref "X_MUX") (pin "13") (pinfunction "S3_13") (pintype "input"))
    )
    (net (code "108") (name "X_SIG") (class "Default")
      (node (ref "X_MUX") (pin "1") (pinfunction "COM_1") (pintype "bidirectional"))
    )
    (net (code "109") (name "Y_C0") (class "Default")
      (node (ref "Y_1") (pin "1") (pinfunction "1_1") (pintype "passive"))
      (node (ref "Y_MUX") (pin "9") (pinfunction "CHAN0_9") (pintype "bidirectional"))
    )
    (net (code "110") (name "Y_C1") (class "Default")
      (node (ref "Y_1") (pin "2") (pinfunction "2_2") (pintype "passive"))
      (node (ref "Y_MUX") (pin "8") (pinfunction "CHAN1_8") (pintype "bidirectional"))
    )
    (net (code "111") (name "Y_C2") (class "Default")
      (node (ref "Y_1") (pin "3") (pinfunction "3_3") (pintype "passive"))
      (node (ref "Y_MUX") (pin "7") (pinfunction "CHAN2_7") (pintype "bidirectional"))
    )
    (net (code "112") (name "Y_C3") (class "Default")
      (node (ref "Y_1") (pin "4") (pinfunction "4_4") (pintype "passive"))
      (node (ref "Y_MUX") (pin "6") (pinfunction "CHAN3_6") (pintype "bidirectional"))
    )
    (net (code "113") (name "Y_C4") (class "Default")
      (node (ref "Y_2") (pin "1") (pinfunction "1_1") (pintype "passive"))
      (node (ref "Y_MUX") (pin "5") (pinfunction "CHAN4_5") (pintype "bidirectional"))
    )
    (net (code "114") (name "Y_C5") (class "Default")
      (node (ref "Y_2") (pin "2") (pinfunction "2_2") (pintype "passive"))
      (node (ref "Y_MUX") (pin "4") (pinfunction "CHAN5_4") (pintype "bidirectional"))
    )
    (net (code "115") (name "Y_C6") (class "Default")
      (node (ref "Y_2") (pin "3") (pinfunction "3_3") (pintype "passive"))
      (node (ref "Y_MUX") (pin "3") (pinfunction "CHAN6_3") (pintype "bidirectional"))
    )
    (net (code "116") (name "Y_C7") (class "Default")
      (node (ref "Y_2") (pin "4") (pinfunction "4_4") (pintype "passive"))
      (node (ref "Y_MUX") (pin "2") (pinfunction "CHAN7_2") (pintype "bidirectional"))
    )
    (net (code "117") (name "Y_C8") (class "Default")
      (node (ref "Y_3") (pin "1") (pinfunction "1_1") (pintype "passive"))
      (node (ref "Y_MUX") (pin "23") (pinfunction "CHAN8_23") (pintype "bidirectional"))
    )
    (net (code "118") (name "Y_C9") (class "Default")
      (node (ref "Y_3") (pin "2") (pinfunction "2_2") (pintype "passive"))
      (node (ref "Y_MUX") (pin "22") (pinfunction "CHAN9_22") (pintype "bidirectional"))
    )
    (net (code "119") (name "Y_C10") (class "Default")
      (node (ref "Y_3") (pin "3") (pinfunction "3_3") (pintype "passive"))
      (node (ref "Y_MUX") (pin "21") (pinfunction "CHAN10_21") (pintype "bidirectional"))
    )
    (net (code "120") (name "Y_C11") (class "Default")
      (node (ref "Y_3") (pin "4") (pinfunction "4_4") (pintype "passive"))
      (node (ref "Y_MUX") (pin "20") (pinfunction "CHAN11_20") (pintype "bidirectional"))
    )
    (net (code "121") (name "Y_C12") (class "Default")
      (node (ref "Y_4") (pin "1") (pinfunction "1_1") (pintype "passive"))
      (node (ref "Y_MUX") (pin "19") (pinfunction "CHAN12_19") (pintype "bidirectional"))
    )
    (net (code "122") (name "Y_C13") (class "Default")
      (node (ref "Y_4") (pin "2") (pinfunction "2_2") (pintype "passive"))
      (node (ref "Y_MUX") (pin "18") (pinfunction "CHAN13_18") (pintype "bidirectional"))
    )
    (net (code "123") (name "Y_C14") (class "Default")
      (node (ref "Y_4") (pin "3") (pinfunction "3_3") (pintype "passive"))
      (node (ref "Y_MUX") (pin "17") (pinfunction "CHAN14_17") (pintype "bidirectional"))
    )
    (net (code "124") (name "Y_C15") (class "Default")
      (node (ref "Y_4") (pin "4") (pinfunction "4_4") (pintype "passive"))
      (node (ref "Y_MUX") (pin "16") (pinfunction "CHAN15_16") (pintype "bidirectional"))
    )
    (net (code "125") (name "Y_S0") (class "Default")
      (node (ref "TEENSY++") (pin "C5") (pinfunction "15,PWM_C5") (pintype "bidirectional"))
      (node (ref "Y_MUX") (pin "10") (pinfunction "S0_10") (pintype "input"))
    )
    (net (code "126") (name "Y_S1") (class "Default")
      (node (ref "TEENSY++") (pin "C4") (pinfunction "14,PWM_C4") (pintype "bidirectional"))
      (node (ref "Y_MUX") (pin "11") (pinfunction "S1_11") (pintype "input"))
    )
    (net (code "127") (name "Y_S2") (class "Default")
      (node (ref "TEENSY++") (pin "C3") (pinfunction "13_C3") (pintype "bidirectional"))
      (node (ref "Y_MUX") (pin "14") (pinfunction "S2_14") (pintype "input"))
    )
    (net (code "128") (name "Y_S3") (class "Default")
      (node (ref "TEENSY++") (pin "C2") (pinfunction "12_C2") (pintype "bidirectional"))
      (node (ref "Y_MUX") (pin "13") (pinfunction "S3_13") (pintype "input"))
    )
    (net (code "129") (name "Y_SIG") (class "Default")
      (node (ref "TEENSY++") (pin "F3") (pinfunction "41,A3_F3") (pintype "bidirectional"))
      (node (ref "Y_MUX") (pin "1") (pinfunction "COM_1") (pintype "bidirectional"))
    )
    (net (code "130") (name "unconnected-(TEENSY++-0,PWM,INT0-PadD0)") (class "Default")
      (node (ref "TEENSY++") (pin "D0") (pinfunction "0,PWM,INT0_D0") (pintype "bidirectional"))
    )
    (net (code "131") (name "unconnected-(TEENSY++-1,PWM,INT1-PadD1)") (class "Default")
      (node (ref "TEENSY++") (pin "D1") (pinfunction "1,PWM,INT1_D1") (pintype "bidirectional"))
    )
    (net (code "132") (name "unconnected-(TEENSY++-2,RX,INT2-PadD2)") (class "Default")
      (node (ref "TEENSY++") (pin "D2") (pinfunction "2,RX,INT2_D2") (pintype "bidirectional"))
    )
    (net (code "133") (name "unconnected-(TEENSY++-3,TX,INT3-PadD3)") (class "Default")
      (node (ref "TEENSY++") (pin "D3") (pinfunction "3,TX,INT3_D3") (pintype "bidirectional"))
    )
    (net (code "134") (name "unconnected-(TEENSY++-16,PWM-PadC6)") (class "Default")
      (node (ref "TEENSY++") (pin "C6") (pinfunction "16,PWM_C6") (pintype "bidirectional"))
    )
    (net (code "135") (name "unconnected-(TEENSY++-17-PadC7)") (class "Default")
      (node (ref "TEENSY++") (pin "C7") (pinfunction "17_C7") (pintype "bidirectional"))
    )
    (net (code "136") (name "unconnected-(TEENSY++-18,INT6-PadE6)") (class "Default")
      (node (ref "TEENSY++") (pin "E6") (pinfunction "18,INT6_E6") (pintype "bidirectional"))
    )
    (net (code "137") (name "unconnected-(TEENSY++-19-PadE7)") (class "Default")
      (node (ref "TEENSY++") (pin "E7") (pinfunction "19_E7") (pintype "bidirectional"))
    )
    (net (code "138") (name "unconnected-(TEENSY++-24,PWM-PadB4)") (class "Default")
      (node (ref "TEENSY++") (pin "B4") (pinfunction "24,PWM_B4") (pintype "bidirectional"))
    )
    (net (code "139") (name "unconnected-(TEENSY++-25,PWM-PadB5)") (class "Default")
      (node (ref "TEENSY++") (pin "B5") (pinfunction "25,PWM_B5") (pintype "bidirectional"))
    )
    (net (code "140") (name "unconnected-(TEENSY++-26,PWM-PadB6)") (class "Default")
      (node (ref "TEENSY++") (pin "B6") (pinfunction "26,PWM_B6") (pintype "bidirectional"))
    )
    (net (code "141") (name "unconnected-(TEENSY++-27,PWM-PadB7)") (class "Default")
      (node (ref "TEENSY++") (pin "B7") (pinfunction "27,PWM_B7") (pintype "bidirectional"))
    )
    (net (code "142") (name "unconnected-(TEENSY++-36,INT4-PadE4)") (class "Default")
      (node (ref "TEENSY++") (pin "E4") (pinfunction "36,INT4_E4") (pintype "bidirectional"))
    )
    (net (code "143") (name "unconnected-(TEENSY++-37,INT5-PadE5)") (class "Default")
      (node (ref "TEENSY++") (pin "E5") (pinfunction "37,INT5_E5") (pintype "bidirectional"))
    )
    (net (code "144") (name "unconnected-(TEENSY++-38,A0-PadF0)") (class "Default")
      (node (ref "TEENSY++") (pin "F0") (pinfunction "38,A0_F0") (pintype "bidirectional"))
    )
    (net (code "145") (name "unconnected-(TEENSY++-39,A1-PadF1)") (class "Default")
      (node (ref "TEENSY++") (pin "F1") (pinfunction "39,A1_F1") (pintype "bidirectional"))
    )
    (net (code "146") (name "unconnected-(TEENSY++-40,A2-PadF2)") (class "Default")
      (node (ref "TEENSY++") (pin "F2") (pinfunction "40,A2_F2") (pintype "bidirectional"))
    )
    (net (code "147") (name "unconnected-(TEENSY++-43,A5-PadF5)") (class "Default")
      (node (ref "TEENSY++") (pin "F5") (pinfunction "43,A5_F5") (pintype "bidirectional"))
    )
    (net (code "148") (name "unconnected-(TEENSY++-44,A6-PadF6)") (class "Default")
      (node (ref "TEENSY++") (pin "F6") (pinfunction "44,A6_F6") (pintype "bidirectional"))
    )
    (net (code "149") (name "unconnected-(TEENSY++-45,A7-PadF7)") (class "Default")
      (node (ref "TEENSY++") (pin "F7") (pinfunction "45,A7_F7") (pintype "bidirectional"))
    )
    (net (code "150") (name "unconnected-(TEENSY++-AREF-PadREF)") (class "Default")
      (node (ref "TEENSY++") (pin "REF") (pinfunction "AREF_REF") (pintype "input"))
    )
    (net (code "151") (name "unconnected-(TEENSY++-Pad+5V)") (class "Default")
      (node (ref "TEENSY++") (pin "+5V") (pinfunction "+5V_+5V") (pintype "power_in"))
    )
    (net (code "152") (name "unconnected-(TEENSY++-_RST-PadRST)") (class "Default")
      (node (ref "TEENSY++") (pin "RST") (pinfunction "_RST_RST") (pintype "input"))
    )
  )
)
